# OpenLux-v1a.net
KiCad netlist of a schematic drawn in EAGLE
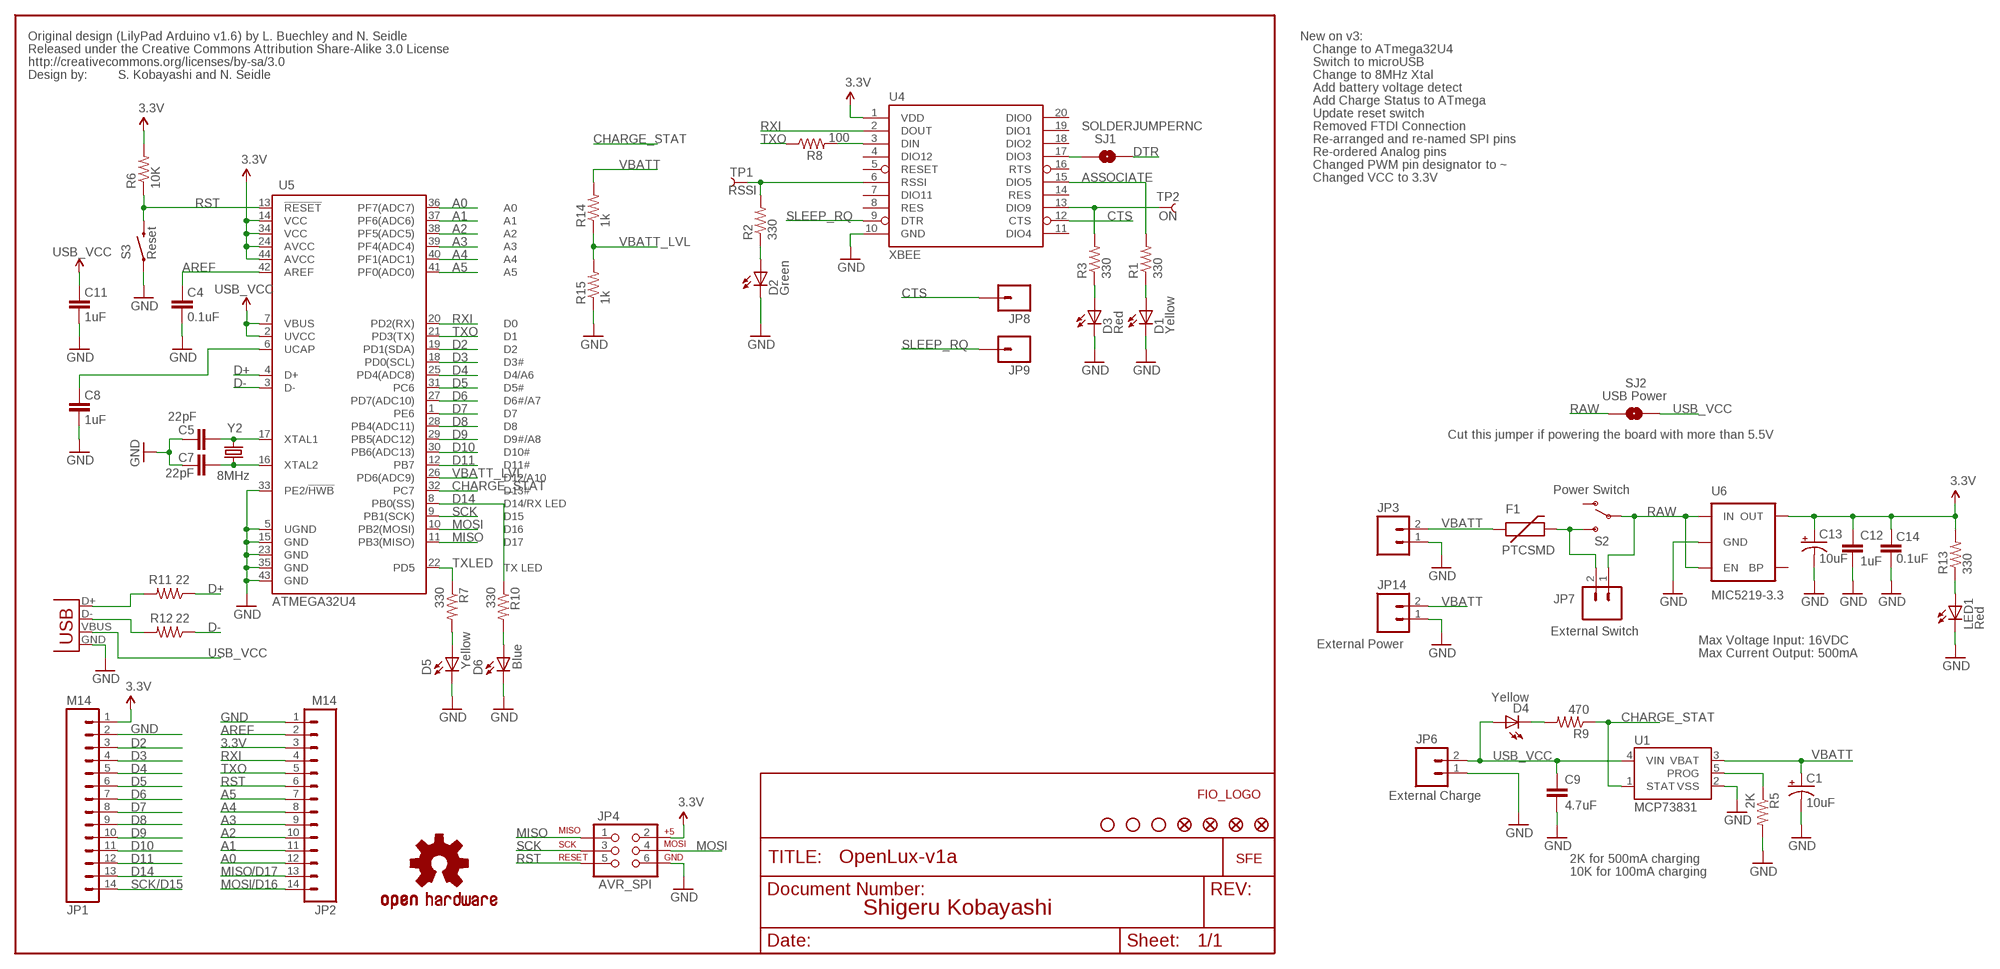
[diagram p0: schematic, sheet 1]

(export (version "E")
  (design (tool "Eeschema 10.0.6"))
  (components
    (comp (ref "C1")
      (value "10uF")
      (footprint "eagle-import:EIA3216")
      (libsource (lib "eagle-import") (part "CAP_POL1206"))
    )
    (comp (ref "C4")
      (value "0.1uF")
      (footprint "eagle-import:0402-CAP")
      (libsource (lib "eagle-import") (part "CAP0402-CAP"))
    )
    (comp (ref "C5")
      (value "22pF")
      (footprint "eagle-import:0402-CAP")
      (libsource (lib "eagle-import") (part "CAP0402-CAP"))
    )
    (comp (ref "C7")
      (value "22pF")
      (footprint "eagle-import:0402-CAP")
      (libsource (lib "eagle-import") (part "CAP0402-CAP"))
    )
    (comp (ref "C8")
      (value "1uF")
      (footprint "eagle-import:0402-CAP")
      (libsource (lib "eagle-import") (part "CAP0402-CAP"))
    )
    (comp (ref "C9")
      (value "4.7uF")
      (footprint "eagle-import:0402-CAP")
      (libsource (lib "eagle-import") (part "CAP0402-CAP"))
    )
    (comp (ref "C11")
      (value "1uF")
      (footprint "eagle-import:0402-CAP")
      (libsource (lib "eagle-import") (part "CAP0402-CAP"))
    )
    (comp (ref "C12")
      (value "1uF")
      (footprint "eagle-import:0402-CAP")
      (libsource (lib "eagle-import") (part "CAP0402-CAP"))
    )
    (comp (ref "C13")
      (value "10uF")
      (footprint "eagle-import:EIA3216")
      (libsource (lib "eagle-import") (part "CAP_POL1206"))
    )
    (comp (ref "C14")
      (value "0.1uF")
      (footprint "eagle-import:0402-CAP")
      (libsource (lib "eagle-import") (part "CAP0402-CAP"))
    )
    (comp (ref "D1")
      (value "Yellow")
      (footprint "eagle-import:LED-0603")
      (libsource (lib "eagle-import") (part "LED0603"))
    )
    (comp (ref "D2")
      (value "Green")
      (footprint "eagle-import:LED-0603")
      (libsource (lib "eagle-import") (part "LED0603"))
    )
    (comp (ref "D3")
      (value "Red")
      (footprint "eagle-import:LED-0603")
      (libsource (lib "eagle-import") (part "LED0603"))
    )
    (comp (ref "D4")
      (value "Yellow")
      (footprint "eagle-import:LED-0603")
      (libsource (lib "eagle-import") (part "LED0603"))
    )
    (comp (ref "D5")
      (value "Yellow")
      (footprint "eagle-import:LED-0603")
      (libsource (lib "eagle-import") (part "LED0603"))
    )
    (comp (ref "D6")
      (value "Blue")
      (footprint "eagle-import:LED-0603")
      (libsource (lib "eagle-import") (part "LED0603"))
    )
    (comp (ref "F1")
      (value "PTCSMD")
      (footprint "eagle-import:PTC-1206")
      (libsource (lib "eagle-import") (part "PTCSMD"))
    )
    (comp (ref "JP1")
      (value "M14")
      (footprint "eagle-import:1X14")
      (libsource (lib "eagle-import") (part "M14"))
    )
    (comp (ref "JP2")
      (value "M14")
      (footprint "eagle-import:1X14")
      (libsource (lib "eagle-import") (part "M14"))
    )
    (comp (ref "JP3")
      (value "M02-JST-2MM-SMT")
      (footprint "eagle-import:JST-2-SMD")
      (libsource (lib "eagle-import") (part "M02-JST-2MM-SMT"))
    )
    (comp (ref "JP4")
      (value "AVR_SPI")
      (footprint "eagle-import:2X3")
      (libsource (lib "eagle-import") (part "AVR_SPI_PRG_6PTH"))
    )
    (comp (ref "JP5")
      (value "STAND-OFF")
      (footprint "eagle-import:STAND-OFF")
      (libsource (lib "eagle-import") (part "STAND-OFF"))
    )
    (comp (ref "JP6")
      (value "External Charge")
      (footprint "eagle-import:1X02")
      (libsource (lib "eagle-import") (part "M02PTH"))
    )
    (comp (ref "JP7")
      (value "External Switch")
      (footprint "eagle-import:1X02")
      (libsource (lib "eagle-import") (part "M02PTH"))
    )
    (comp (ref "JP8")
      (value "M01PTH")
      (footprint "eagle-import:1X01")
      (libsource (lib "eagle-import") (part "M01PTH"))
    )
    (comp (ref "JP9")
      (value "M01PTH")
      (footprint "eagle-import:1X01")
      (libsource (lib "eagle-import") (part "M01PTH"))
    )
    (comp (ref "JP10")
      (value "FIDUCIALUFIDUCIAL")
      (footprint "eagle-import:FIDUCIAL-1X2")
      (libsource (lib "eagle-import") (part "FIDUCIAL1X2"))
    )
    (comp (ref "JP11")
      (value "FIDUCIALUFIDUCIAL")
      (footprint "eagle-import:FIDUCIAL-1X2")
      (libsource (lib "eagle-import") (part "FIDUCIAL1X2"))
    )
    (comp (ref "JP12")
      (value "FIDUCIALUFIDUCIAL")
      (footprint "eagle-import:FIDUCIAL-1X2")
      (libsource (lib "eagle-import") (part "FIDUCIAL1X2"))
    )
    (comp (ref "JP13")
      (value "FIDUCIALUFIDUCIAL")
      (footprint "eagle-import:FIDUCIAL-1X2")
      (libsource (lib "eagle-import") (part "FIDUCIAL1X2"))
    )
    (comp (ref "JP14")
      (value "External Power")
      (footprint "eagle-import:1X02")
      (libsource (lib "eagle-import") (part "M02PTH"))
    )
    (comp (ref "JP16")
      (value "STAND-OFF")
      (footprint "eagle-import:STAND-OFF")
      (libsource (lib "eagle-import") (part "STAND-OFF"))
    )
    (comp (ref "JP17")
      (value "STAND-OFF")
      (footprint "eagle-import:STAND-OFF")
      (libsource (lib "eagle-import") (part "STAND-OFF"))
    )
    (comp (ref "LED1")
      (value "Red")
      (footprint "eagle-import:LED-0603")
      (libsource (lib "eagle-import") (part "LED0603"))
    )
    (comp (ref "R1")
      (value "330")
      (footprint "eagle-import:0402-RES")
      (libsource (lib "eagle-import") (part "RESISTOR0402-RES"))
    )
    (comp (ref "R2")
      (value "330")
      (footprint "eagle-import:0402-RES")
      (libsource (lib "eagle-import") (part "RESISTOR0402-RES"))
    )
    (comp (ref "R3")
      (value "330")
      (footprint "eagle-import:0402-RES")
      (libsource (lib "eagle-import") (part "RESISTOR0402-RES"))
    )
    (comp (ref "R5")
      (value "2K")
      (footprint "eagle-import:0402-RES")
      (libsource (lib "eagle-import") (part "RESISTOR0402-RES"))
    )
    (comp (ref "R6")
      (value "10K")
      (footprint "eagle-import:0402-RES")
      (libsource (lib "eagle-import") (part "RESISTOR0402-RES"))
    )
    (comp (ref "R7")
      (value "330")
      (footprint "eagle-import:0402-RES")
      (libsource (lib "eagle-import") (part "RESISTOR0402-RES"))
    )
    (comp (ref "R8")
      (value "100")
      (footprint "eagle-import:0402-RES")
      (libsource (lib "eagle-import") (part "RESISTOR0402-RES"))
    )
    (comp (ref "R9")
      (value "470")
      (footprint "eagle-import:0402-RES")
      (libsource (lib "eagle-import") (part "RESISTOR0402-RES"))
    )
    (comp (ref "R10")
      (value "330")
      (footprint "eagle-import:0402-RES")
      (libsource (lib "eagle-import") (part "RESISTOR0402-RES"))
    )
    (comp (ref "R11")
      (value "22")
      (footprint "eagle-import:0402-RES")
      (libsource (lib "eagle-import") (part "RESISTOR0402-RES"))
    )
    (comp (ref "R12")
      (value "22")
      (footprint "eagle-import:0402-RES")
      (libsource (lib "eagle-import") (part "RESISTOR0402-RES"))
    )
    (comp (ref "R13")
      (value "330")
      (footprint "eagle-import:0402-RES")
      (libsource (lib "eagle-import") (part "RESISTOR0402-RES"))
    )
    (comp (ref "R14")
      (value "1k")
      (footprint "eagle-import:0402-RES")
      (libsource (lib "eagle-import") (part "RESISTOR0402-RES"))
    )
    (comp (ref "R15")
      (value "1k")
      (footprint "eagle-import:0402-RES")
      (libsource (lib "eagle-import") (part "RESISTOR0402-RES"))
    )
    (comp (ref "S2")
      (value "Power Switch")
      (footprint "eagle-import:AYZ0202")
      (libsource (lib "eagle-import") (part "SWITCH-SPSTSMD"))
    )
    (comp (ref "S3")
      (value "Reset")
      (footprint "eagle-import:TACTILE_SWITCH_SMD")
      (libsource (lib "eagle-import") (part "SWITCH-MOMENTARY-2SMD"))
    )
    (comp (ref "SJ1")
      (value "SOLDERJUMPERNC")
      (footprint "eagle-import:SJ_2S")
      (libsource (lib "eagle-import") (part "SOLDERJUMPERNC"))
    )
    (comp (ref "SJ2")
      (value "USB Power")
      (footprint "eagle-import:SJ_2S-TRACE")
      (libsource (lib "eagle-import") (part "SOLDERJUMPERTRACE"))
    )
    (comp (ref "TP1")
      (value "RSSI")
      (footprint "eagle-import:PAD.03X.05")
      (libsource (lib "eagle-import") (part "TEST-POINT3X5"))
    )
    (comp (ref "TP2")
      (value "ON")
      (footprint "eagle-import:PAD.03X.05")
      (libsource (lib "eagle-import") (part "TEST-POINT3X5"))
    )
    (comp (ref "U$1")
      (value "LOGO-SFENEW")
      (footprint "eagle-import:SFE-NEW-WEBLOGO")
      (libsource (lib "eagle-import") (part "LOGO-SFENEW"))
    )
    (comp (ref "U$2")
      (value "OSHW-LOGOS")
      (footprint "eagle-import:OSHW-LOGO-S")
      (libsource (lib "eagle-import") (part "OSHW-LOGOS"))
    )
    (comp (ref "U$3")
      (value "CREATIVE_COMMONS")
      (footprint "eagle-import:CREATIVE_COMMONS")
      (libsource (lib "eagle-import") (part "CREATIVE_COMMONS"))
    )
    (comp (ref "U$6")
      (value "FIO_LOGOV2")
      (footprint "eagle-import:FUNNEL_LOGO_BOTTOM_V2")
      (libsource (lib "eagle-import") (part "FIO_LOGOV2"))
    )
    (comp (ref "U1")
      (value "MCP73831")
      (footprint "eagle-import:SOT23-5")
      (libsource (lib "eagle-import") (part "MCP73831"))
    )
    (comp (ref "U4")
      (value "XBEE")
      (footprint "eagle-import:XBEE-SMD")
      (libsource (lib "eagle-import") (part "XBEE-1B3"))
    )
    (comp (ref "U5")
      (value "ATMEGA32U4")
      (footprint "eagle-import:QFN-44-NOPAD")
      (libsource (lib "eagle-import") (part "ATMEGA32U4QFN2"))
    )
    (comp (ref "U6")
      (value "MIC5219-3.3")
      (footprint "eagle-import:SOT23-5")
      (libsource (lib "eagle-import") (part "V_REG_LDOSMD"))
    )
    (comp (ref "X2")
      (value "USB-MICROB")
      (footprint "eagle-import:USB-MICROB")
      (libsource (lib "eagle-import") (part "USB-MICROB"))
    )
    (comp (ref "Y2")
      (value "8MHz")
      (footprint "eagle-import:CRYSTAL-SMD-5X3")
      (libsource (lib "eagle-import") (part "CRYSTAL5X3"))
    )
  )
  (nets
    (net (code "1") (name "/A0") (class "Default")
      (node (ref "JP2") (pin "12") (pinfunction "12_12") (pintype "passive"))
      (node (ref "U5") (pin "36") (pinfunction "PF7(ADC7)_36") (pintype "bidirectional"))
    )
    (net (code "2") (name "/A1") (class "Default")
      (node (ref "JP2") (pin "11") (pinfunction "11_11") (pintype "passive"))
      (node (ref "U5") (pin "37") (pinfunction "PF6(ADC6)_37") (pintype "bidirectional"))
    )
    (net (code "3") (name "/A2") (class "Default")
      (node (ref "JP2") (pin "10") (pinfunction "10_10") (pintype "passive"))
      (node (ref "U5") (pin "38") (pinfunction "PF5(ADC5)_38") (pintype "bidirectional"))
    )
    (net (code "4") (name "/A3") (class "Default")
      (node (ref "JP2") (pin "9") (pinfunction "9_9") (pintype "passive"))
      (node (ref "U5") (pin "39") (pinfunction "PF4(ADC4)_39") (pintype "bidirectional"))
    )
    (net (code "5") (name "/A4") (class "Default")
      (node (ref "JP2") (pin "8") (pinfunction "8_8") (pintype "passive"))
      (node (ref "U5") (pin "40") (pinfunction "PF1(ADC1)_40") (pintype "bidirectional"))
    )
    (net (code "6") (name "/A5") (class "Default")
      (node (ref "JP2") (pin "7") (pinfunction "7_7") (pintype "passive"))
      (node (ref "U5") (pin "41") (pinfunction "PF0(ADC0)_41") (pintype "bidirectional"))
    )
    (net (code "7") (name "/AREF") (class "Default")
      (node (ref "C4") (pin "2") (pinfunction "2_2") (pintype "passive"))
      (node (ref "JP2") (pin "2") (pinfunction "2_2") (pintype "passive"))
      (node (ref "U5") (pin "42") (pinfunction "AREF_42") (pintype "bidirectional"))
    )
    (net (code "8") (name "/ASSOCIATE") (class "Default")
      (node (ref "R1") (pin "2") (pinfunction "2_2") (pintype "passive"))
      (node (ref "U4") (pin "15") (pinfunction "DIO5_15") (pintype "bidirectional"))
    )
    (net (code "9") (name "/CHARGE_STAT") (class "Default")
      (node (ref "R9") (pin "1") (pinfunction "1_1") (pintype "passive"))
      (node (ref "U1") (pin "1") (pinfunction "STAT_1") (pintype "output"))
      (node (ref "U5") (pin "32") (pinfunction "PC7_32") (pintype "bidirectional"))
    )
    (net (code "10") (name "/CTS") (class "Default")
      (node (ref "JP8") (pin "1") (pinfunction "1_1") (pintype "passive"))
      (node (ref "U4") (pin "12") (pinfunction "CTS_12") (pintype "output"))
    )
    (net (code "11") (name "/D+") (class "Default")
      (node (ref "R11") (pin "1") (pinfunction "1_1") (pintype "passive"))
      (node (ref "U5") (pin "4") (pinfunction "D+_4") (pintype "bidirectional"))
    )
    (net (code "12") (name "/D-") (class "Default")
      (node (ref "R12") (pin "1") (pinfunction "1_1") (pintype "passive"))
      (node (ref "U5") (pin "3") (pinfunction "D-_3") (pintype "bidirectional"))
    )
    (net (code "13") (name "/D2") (class "Default")
      (node (ref "JP1") (pin "3") (pinfunction "3_3") (pintype "passive"))
      (node (ref "U5") (pin "19") (pinfunction "PD1(SDA)_19") (pintype "bidirectional"))
    )
    (net (code "14") (name "/D3") (class "Default")
      (node (ref "JP1") (pin "4") (pinfunction "4_4") (pintype "passive"))
      (node (ref "U5") (pin "18") (pinfunction "PD0(SCL)_18") (pintype "bidirectional"))
    )
    (net (code "15") (name "/D4") (class "Default")
      (node (ref "JP1") (pin "5") (pinfunction "5_5") (pintype "passive"))
      (node (ref "U5") (pin "25") (pinfunction "PD4(ADC8)_25") (pintype "bidirectional"))
    )
    (net (code "16") (name "/D5") (class "Default")
      (node (ref "JP1") (pin "6") (pinfunction "6_6") (pintype "passive"))
      (node (ref "U5") (pin "31") (pinfunction "PC6_31") (pintype "bidirectional"))
    )
    (net (code "17") (name "/D6") (class "Default")
      (node (ref "JP1") (pin "7") (pinfunction "7_7") (pintype "passive"))
      (node (ref "U5") (pin "27") (pinfunction "PD7(ADC10)_27") (pintype "bidirectional"))
    )
    (net (code "18") (name "/D7") (class "Default")
      (node (ref "JP1") (pin "8") (pinfunction "8_8") (pintype "passive"))
      (node (ref "U5") (pin "1") (pinfunction "PE6_1") (pintype "bidirectional"))
    )
    (net (code "19") (name "/D8") (class "Default")
      (node (ref "JP1") (pin "9") (pinfunction "9_9") (pintype "passive"))
      (node (ref "U5") (pin "28") (pinfunction "PB4(ADC11)_28") (pintype "bidirectional"))
    )
    (net (code "20") (name "/D9") (class "Default")
      (node (ref "JP1") (pin "10") (pinfunction "10_10") (pintype "passive"))
      (node (ref "U5") (pin "29") (pinfunction "PB5(ADC12)_29") (pintype "bidirectional"))
    )
    (net (code "21") (name "/D10") (class "Default")
      (node (ref "JP1") (pin "11") (pinfunction "11_11") (pintype "passive"))
      (node (ref "U5") (pin "30") (pinfunction "PB6(ADC13)_30") (pintype "bidirectional"))
    )
    (net (code "22") (name "/D11") (class "Default")
      (node (ref "JP1") (pin "12") (pinfunction "12_12") (pintype "passive"))
      (node (ref "U5") (pin "12") (pinfunction "PB7_12") (pintype "bidirectional"))
    )
    (net (code "23") (name "/D14") (class "Default")
      (node (ref "JP1") (pin "13") (pinfunction "13_13") (pintype "passive"))
      (node (ref "R10") (pin "1") (pinfunction "1_1") (pintype "passive"))
      (node (ref "U5") (pin "8") (pinfunction "PB0(SS)_8") (pintype "bidirectional"))
    )
    (net (code "24") (name "/DTR") (class "Default")
      (node (ref "SJ1") (pin "2") (pinfunction "2_2") (pintype "passive"))
    )
    (net (code "25") (name "/MISO") (class "Default")
      (node (ref "JP2") (pin "13") (pinfunction "13_13") (pintype "passive"))
      (node (ref "JP4") (pin "1") (pinfunction "1_1") (pintype "passive"))
      (node (ref "U5") (pin "11") (pinfunction "PB3(MISO)_11") (pintype "bidirectional"))
    )
    (net (code "26") (name "/MOSI") (class "Default")
      (node (ref "JP2") (pin "14") (pinfunction "14_14") (pintype "passive"))
      (node (ref "JP4") (pin "4") (pinfunction "4_4") (pintype "passive"))
      (node (ref "U5") (pin "10") (pinfunction "PB2(MOSI)_10") (pintype "bidirectional"))
    )
    (net (code "27") (name "/RAW") (class "Default")
      (node (ref "JP7") (pin "1") (pinfunction "1_1") (pintype "passive"))
      (node (ref "S2") (pin "2") (pinfunction "P_2") (pintype "passive"))
      (node (ref "SJ2") (pin "1") (pinfunction "1_1") (pintype "passive"))
      (node (ref "U6") (pin "1") (pinfunction "IN_1") (pintype "input"))
      (node (ref "U6") (pin "3") (pinfunction "EN_3") (pintype "input"))
    )
    (net (code "28") (name "/RST") (class "Default")
      (node (ref "JP2") (pin "6") (pinfunction "6_6") (pintype "passive"))
      (node (ref "JP4") (pin "5") (pinfunction "5_5") (pintype "passive"))
      (node (ref "R6") (pin "1") (pinfunction "1_1") (pintype "passive"))
      (node (ref "S3") (pin "3") (pinfunction "2_3") (pintype "passive"))
      (node (ref "U5") (pin "13") (pinfunction "~{RESET}_13") (pintype "bidirectional"))
    )
    (net (code "29") (name "/RXI") (class "Default")
      (node (ref "JP2") (pin "4") (pinfunction "4_4") (pintype "passive"))
      (node (ref "U4") (pin "2") (pinfunction "DOUT_2") (pintype "output"))
      (node (ref "U5") (pin "20") (pinfunction "PD2(RX)_20") (pintype "bidirectional"))
    )
    (net (code "30") (name "/SCK") (class "Default")
      (node (ref "JP1") (pin "14") (pinfunction "14_14") (pintype "passive"))
      (node (ref "JP4") (pin "3") (pinfunction "3_3") (pintype "passive"))
      (node (ref "U5") (pin "9") (pinfunction "PB1(SCK)_9") (pintype "bidirectional"))
    )
    (net (code "31") (name "/SLEEP_RQ") (class "Default")
      (node (ref "JP9") (pin "1") (pinfunction "1_1") (pintype "passive"))
      (node (ref "U4") (pin "9") (pinfunction "DTR_9") (pintype "bidirectional"))
    )
    (net (code "32") (name "/TXLED") (class "Default")
      (node (ref "R7") (pin "1") (pinfunction "1_1") (pintype "passive"))
      (node (ref "U5") (pin "22") (pinfunction "PD5_22") (pintype "bidirectional"))
    )
    (net (code "33") (name "/TXO") (class "Default")
      (node (ref "JP2") (pin "5") (pinfunction "5_5") (pintype "passive"))
      (node (ref "R8") (pin "1") (pinfunction "1_1") (pintype "passive"))
      (node (ref "U5") (pin "21") (pinfunction "PD3(TX)_21") (pintype "bidirectional"))
    )
    (net (code "34") (name "/VBATT") (class "Default")
      (node (ref "C1") (pin "A") (pinfunction "+_A") (pintype "passive"))
      (node (ref "F1") (pin "1") (pinfunction "1_1") (pintype "bidirectional"))
      (node (ref "JP14") (pin "2") (pinfunction "2_2") (pintype "passive"))
      (node (ref "JP3") (pin "2") (pinfunction "2_2") (pintype "passive"))
      (node (ref "R14") (pin "2") (pinfunction "2_2") (pintype "passive"))
      (node (ref "U1") (pin "3") (pinfunction "VBAT_3") (pintype "power_in"))
    )
    (net (code "35") (name "/VBATT_LVL") (class "Default")
      (node (ref "R14") (pin "1") (pinfunction "1_1") (pintype "passive"))
      (node (ref "R15") (pin "2") (pinfunction "2_2") (pintype "passive"))
      (node (ref "U5") (pin "26") (pinfunction "PD6(ADC9)_26") (pintype "bidirectional"))
    )
    (net (code "36") (name "3.3V") (class "Default")
      (node (ref "C12") (pin "1") (pinfunction "1_1") (pintype "passive"))
      (node (ref "C13") (pin "A") (pinfunction "+_A") (pintype "passive"))
      (node (ref "C14") (pin "2") (pinfunction "2_2") (pintype "passive"))
      (node (ref "JP1") (pin "1") (pinfunction "1_1") (pintype "passive"))
      (node (ref "JP2") (pin "3") (pinfunction "3_3") (pintype "passive"))
      (node (ref "JP4") (pin "2") (pinfunction "2_2") (pintype "passive"))
      (node (ref "R13") (pin "2") (pinfunction "2_2") (pintype "passive"))
      (node (ref "R6") (pin "2") (pinfunction "2_2") (pintype "passive"))
      (node (ref "U4") (pin "1") (pinfunction "VDD_1") (pintype "power_in"))
      (node (ref "U5") (pin "14") (pinfunction "VCC_14") (pintype "bidirectional"))
      (node (ref "U5") (pin "24") (pinfunction "AVCC_24") (pintype "bidirectional"))
      (node (ref "U5") (pin "34") (pinfunction "VCC_34") (pintype "bidirectional"))
      (node (ref "U5") (pin "44") (pinfunction "AVCC_44") (pintype "bidirectional"))
      (node (ref "U6") (pin "5") (pinfunction "OUT_5") (pintype "passive"))
    )
    (net (code "37") (name "GND") (class "Default")
      (node (ref "C1") (pin "C") (pinfunction "-_C") (pintype "passive"))
      (node (ref "C11") (pin "1") (pinfunction "1_1") (pintype "passive"))
      (node (ref "C12") (pin "2") (pinfunction "2_2") (pintype "passive"))
      (node (ref "C13") (pin "C") (pinfunction "-_C") (pintype "passive"))
      (node (ref "C14") (pin "1") (pinfunction "1_1") (pintype "passive"))
      (node (ref "C4") (pin "1") (pinfunction "1_1") (pintype "passive"))
      (node (ref "C5") (pin "2") (pinfunction "2_2") (pintype "passive"))
      (node (ref "C7") (pin "2") (pinfunction "2_2") (pintype "passive"))
      (node (ref "C8") (pin "1") (pinfunction "1_1") (pintype "passive"))
      (node (ref "C9") (pin "2") (pinfunction "2_2") (pintype "passive"))
      (node (ref "D1") (pin "C") (pinfunction "C_C") (pintype "passive"))
      (node (ref "D2") (pin "C") (pinfunction "C_C") (pintype "passive"))
      (node (ref "D3") (pin "C") (pinfunction "C_C") (pintype "passive"))
      (node (ref "D5") (pin "C") (pinfunction "C_C") (pintype "passive"))
      (node (ref "D6") (pin "C") (pinfunction "C_C") (pintype "passive"))
      (node (ref "JP1") (pin "2") (pinfunction "2_2") (pintype "passive"))
      (node (ref "JP14") (pin "1") (pinfunction "1_1") (pintype "passive"))
      (node (ref "JP2") (pin "1") (pinfunction "1_1") (pintype "passive"))
      (node (ref "JP3") (pin "1") (pinfunction "1_1") (pintype "passive"))
      (node (ref "JP4") (pin "6") (pinfunction "6_6") (pintype "passive"))
      (node (ref "JP6") (pin "1") (pinfunction "1_1") (pintype "passive"))
      (node (ref "LED1") (pin "C") (pinfunction "C_C") (pintype "passive"))
      (node (ref "R15") (pin "1") (pinfunction "1_1") (pintype "passive"))
      (node (ref "R5") (pin "2") (pinfunction "2_2") (pintype "passive"))
      (node (ref "S3") (pin "1") (pinfunction "1_1") (pintype "passive"))
      (node (ref "U1") (pin "2") (pinfunction "VSS_2") (pintype "power_in"))
      (node (ref "U4") (pin "10") (pinfunction "GND_10") (pintype "power_in"))
      (node (ref "U5") (pin "15") (pinfunction "GND_15") (pintype "bidirectional"))
      (node (ref "U5") (pin "23") (pinfunction "GND_23") (pintype "bidirectional"))
      (node (ref "U5") (pin "33") (pinfunction "PE2/~{HWB}_33") (pintype "bidirectional"))
      (node (ref "U5") (pin "35") (pinfunction "GND_35") (pintype "bidirectional"))
      (node (ref "U5") (pin "43") (pinfunction "GND_43") (pintype "bidirectional"))
      (node (ref "U5") (pin "5") (pinfunction "UGND_5") (pintype "bidirectional"))
      (node (ref "U6") (pin "2") (pinfunction "GND_2") (pintype "input"))
      (node (ref "X2") (pin "GND") (pinfunction "GND_GND") (pintype "bidirectional"))
    )
    (net (code "38") (name "Net-(D1-PadA)") (class "Default")
      (node (ref "D1") (pin "A") (pinfunction "A_A") (pintype "passive"))
      (node (ref "R1") (pin "1") (pinfunction "1_1") (pintype "passive"))
    )
    (net (code "39") (name "Net-(D2-PadA)") (class "Default")
      (node (ref "D2") (pin "A") (pinfunction "A_A") (pintype "passive"))
      (node (ref "R2") (pin "1") (pinfunction "1_1") (pintype "passive"))
    )
    (net (code "40") (name "Net-(D3-PadA)") (class "Default")
      (node (ref "D3") (pin "A") (pinfunction "A_A") (pintype "passive"))
      (node (ref "R3") (pin "1") (pinfunction "1_1") (pintype "passive"))
    )
    (net (code "41") (name "Net-(D4-PadC)") (class "Default")
      (node (ref "D4") (pin "C") (pinfunction "C_C") (pintype "passive"))
      (node (ref "R9") (pin "2") (pinfunction "2_2") (pintype "passive"))
    )
    (net (code "42") (name "Net-(D5-PadA)") (class "Default")
      (node (ref "D5") (pin "A") (pinfunction "A_A") (pintype "passive"))
      (node (ref "R7") (pin "2") (pinfunction "2_2") (pintype "passive"))
    )
    (net (code "43") (name "Net-(D6-PadA)") (class "Default")
      (node (ref "D6") (pin "A") (pinfunction "A_A") (pintype "passive"))
      (node (ref "R10") (pin "2") (pinfunction "2_2") (pintype "passive"))
    )
    (net (code "44") (name "Net-(LED1-PadA)") (class "Default")
      (node (ref "LED1") (pin "A") (pinfunction "A_A") (pintype "passive"))
      (node (ref "R13") (pin "1") (pinfunction "1_1") (pintype "passive"))
    )
    (net (code "45") (name "Net-(R11-Pad2)") (class "Default")
      (node (ref "R11") (pin "2") (pinfunction "2_2") (pintype "passive"))
      (node (ref "X2") (pin "D+") (pinfunction "D+_D+") (pintype "bidirectional"))
    )
    (net (code "46") (name "Net-(R12-Pad2)") (class "Default")
      (node (ref "R12") (pin "2") (pinfunction "2_2") (pintype "passive"))
      (node (ref "X2") (pin "D-") (pinfunction "D-_D-") (pintype "bidirectional"))
    )
    (net (code "47") (name "Net-(S2-S)") (class "Default")
      (node (ref "F1") (pin "2") (pinfunction "2_2") (pintype "bidirectional"))
      (node (ref "JP7") (pin "2") (pinfunction "2_2") (pintype "passive"))
      (node (ref "S2") (pin "3") (pinfunction "S_3") (pintype "passive"))
    )
    (net (code "48") (name "Net-(TP1-1)") (class "Default")
      (node (ref "R2") (pin "2") (pinfunction "2_2") (pintype "passive"))
      (node (ref "TP1") (pin "P$1") (pinfunction "1_P$1") (pintype "bidirectional"))
      (node (ref "U4") (pin "6") (pinfunction "RSSI_6") (pintype "bidirectional"))
    )
    (net (code "49") (name "Net-(TP2-1)") (class "Default")
      (node (ref "R3") (pin "2") (pinfunction "2_2") (pintype "passive"))
      (node (ref "TP2") (pin "P$1") (pinfunction "1_P$1") (pintype "bidirectional"))
      (node (ref "U4") (pin "13") (pinfunction "DIO9_13") (pintype "bidirectional"))
    )
    (net (code "50") (name "Net-(U1-PROG)") (class "Default")
      (node (ref "R5") (pin "1") (pinfunction "1_1") (pintype "passive"))
      (node (ref "U1") (pin "5") (pinfunction "PROG_5") (pintype "input"))
    )
    (net (code "51") (name "Net-(U4-DIN)") (class "Default")
      (node (ref "R8") (pin "2") (pinfunction "2_2") (pintype "passive"))
      (node (ref "U4") (pin "3") (pinfunction "DIN_3") (pintype "input"))
    )
    (net (code "52") (name "Net-(U4-DIO3)") (class "Default")
      (node (ref "SJ1") (pin "1") (pinfunction "1_1") (pintype "passive"))
      (node (ref "U4") (pin "17") (pinfunction "DIO3_17") (pintype "bidirectional"))
    )
    (net (code "53") (name "Net-(U5-UCAP)") (class "Default")
      (node (ref "C8") (pin "2") (pinfunction "2_2") (pintype "passive"))
      (node (ref "U5") (pin "6") (pinfunction "UCAP_6") (pintype "bidirectional"))
    )
    (net (code "54") (name "Net-(U5-XTAL1)") (class "Default")
      (node (ref "C5") (pin "1") (pinfunction "1_1") (pintype "passive"))
      (node (ref "U5") (pin "17") (pinfunction "XTAL1_17") (pintype "bidirectional"))
      (node (ref "Y2") (pin "3") (pinfunction "2_3") (pintype "passive"))
    )
    (net (code "55") (name "Net-(U5-XTAL2)") (class "Default")
      (node (ref "C7") (pin "1") (pinfunction "1_1") (pintype "passive"))
      (node (ref "U5") (pin "16") (pinfunction "XTAL2_16") (pintype "bidirectional"))
      (node (ref "Y2") (pin "1") (pinfunction "1_1") (pintype "passive"))
    )
    (net (code "56") (name "USB_VCC") (class "Default")
      (node (ref "C11") (pin "2") (pinfunction "2_2") (pintype "passive"))
      (node (ref "C9") (pin "1") (pinfunction "1_1") (pintype "passive"))
      (node (ref "D4") (pin "A") (pinfunction "A_A") (pintype "passive"))
      (node (ref "JP6") (pin "2") (pinfunction "2_2") (pintype "passive"))
      (node (ref "SJ2") (pin "2") (pinfunction "2_2") (pintype "passive"))
      (node (ref "U1") (pin "4") (pinfunction "VIN_4") (pintype "power_in"))
      (node (ref "U5") (pin "2") (pinfunction "UVCC_2") (pintype "bidirectional"))
      (node (ref "U5") (pin "7") (pinfunction "VBUS_7") (pintype "bidirectional"))
      (node (ref "X2") (pin "VBUS") (pinfunction "VBUS_VBUS") (pintype "bidirectional"))
    )
    (net (code "57") (name "unconnected-(S2-O-Pad1)") (class "Default")
      (node (ref "S2") (pin "1") (pinfunction "O_1") (pintype "passive"))
    )
    (net (code "58") (name "unconnected-(U4-DIO0-Pad20)") (class "Default")
      (node (ref "U4") (pin "20") (pinfunction "DIO0_20") (pintype "bidirectional"))
    )
    (net (code "59") (name "unconnected-(U4-DIO1-Pad19)") (class "Default")
      (node (ref "U4") (pin "19") (pinfunction "DIO1_19") (pintype "bidirectional"))
    )
    (net (code "60") (name "unconnected-(U4-DIO2-Pad18)") (class "Default")
      (node (ref "U4") (pin "18") (pinfunction "DIO2_18") (pintype "bidirectional"))
    )
    (net (code "61") (name "unconnected-(U4-DIO4-Pad11)") (class "Default")
      (node (ref "U4") (pin "11") (pinfunction "DIO4_11") (pintype "bidirectional"))
    )
    (net (code "62") (name "unconnected-(U4-DIO11-Pad7)") (class "Default")
      (node (ref "U4") (pin "7") (pinfunction "DIO11_7") (pintype "bidirectional"))
    )
    (net (code "63") (name "unconnected-(U4-DIO12-Pad4)") (class "Default")
      (node (ref "U4") (pin "4") (pinfunction "DIO12_4") (pintype "bidirectional"))
    )
    (net (code "64") (name "unconnected-(U4-RES-Pad8)") (class "Default")
      (node (ref "U4") (pin "8") (pinfunction "RES_8") (pintype "bidirectional"))
    )
    (net (code "65") (name "unconnected-(U4-RES-Pad14)") (class "Default")
      (node (ref "U4") (pin "14") (pinfunction "RES_14") (pintype "bidirectional"))
    )
    (net (code "66") (name "unconnected-(U4-RESET-Pad5)") (class "Default")
      (node (ref "U4") (pin "5") (pinfunction "RESET_5") (pintype "input"))
    )
    (net (code "67") (name "unconnected-(U4-RTS-Pad16)") (class "Default")
      (node (ref "U4") (pin "16") (pinfunction "RTS_16") (pintype "input"))
    )
    (net (code "68") (name "unconnected-(U6-BP-Pad4)") (class "Default")
      (node (ref "U6") (pin "4") (pinfunction "BP_4") (pintype "input"))
    )
  )
)
